# AM438x_EPOS_EVM_PMconnect.net
KiCad netlist of a schematic drawn in Altium Designer
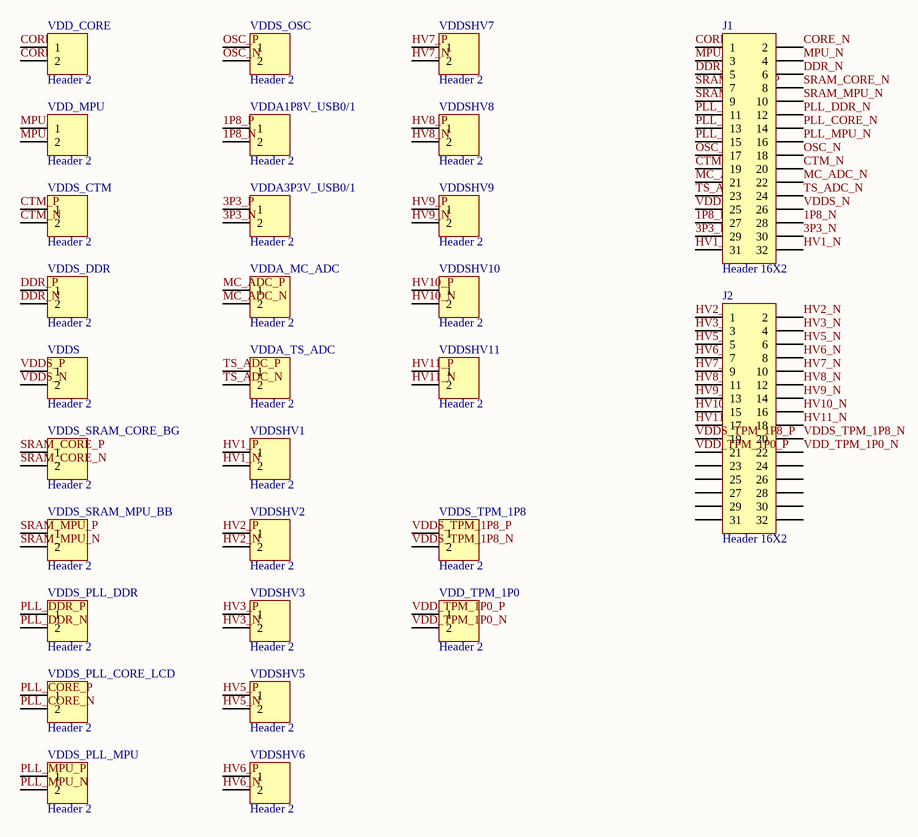
[diagram p0: AM438x_EPOS_EVM_PMconnect.SchDoc]

(export (version "E")
  (design (tool "Eeschema 10.0.6"))
  (components
    (comp (ref "J1")
      (value "Header 16X2")
      (footprint "HDR2X16")
      (description "Header, 16-Pin, Dual row")
      (fields (field (name "PUBLISHER") "Altium Limited"))
      (libsource (lib "Miscellaneous Connectors") (part "Header 16X2"))
    )
    (comp (ref "J2")
      (value "Header 16X2")
      (footprint "HDR2X16")
      (description "Header, 16-Pin, Dual row")
      (fields (field (name "PUBLISHER") "Altium Limited"))
      (libsource (lib "Miscellaneous Connectors") (part "Header 16X2"))
    )
    (comp (ref "VDDA1P8V_USB0/1")
      (value "Header 2")
      (footprint "HDR1X2")
      (description "Header, 2-Pin")
      (fields (field (name "PUBLISHER") "Altium Limited"))
      (libsource (lib "Miscellaneous Connectors") (part "Header 2"))
    )
    (comp (ref "VDDA3P3V_USB0/1")
      (value "Header 2")
      (footprint "HDR1X2")
      (description "Header, 2-Pin")
      (fields (field (name "PUBLISHER") "Altium Limited"))
      (libsource (lib "Miscellaneous Connectors") (part "Header 2"))
    )
    (comp (ref "VDDA_MC_ADC")
      (value "Header 2")
      (footprint "HDR1X2")
      (description "Header, 2-Pin")
      (fields (field (name "PUBLISHER") "Altium Limited"))
      (libsource (lib "Miscellaneous Connectors") (part "Header 2"))
    )
    (comp (ref "VDDA_TS_ADC")
      (value "Header 2")
      (footprint "HDR1X2")
      (description "Header, 2-Pin")
      (fields (field (name "PUBLISHER") "Altium Limited"))
      (libsource (lib "Miscellaneous Connectors") (part "Header 2"))
    )
    (comp (ref "VDDS")
      (value "Header 2")
      (footprint "HDR1X2")
      (description "Header, 2-Pin")
      (fields (field (name "PUBLISHER") "Altium Limited"))
      (libsource (lib "Miscellaneous Connectors") (part "Header 2"))
    )
    (comp (ref "VDDSHV1")
      (value "Header 2")
      (footprint "HDR1X2")
      (description "Header, 2-Pin")
      (fields (field (name "PUBLISHER") "Altium Limited"))
      (libsource (lib "Miscellaneous Connectors") (part "Header 2"))
    )
    (comp (ref "VDDSHV2")
      (value "Header 2")
      (footprint "HDR1X2")
      (description "Header, 2-Pin")
      (fields (field (name "PUBLISHER") "Altium Limited"))
      (libsource (lib "Miscellaneous Connectors") (part "Header 2"))
    )
    (comp (ref "VDDSHV3")
      (value "Header 2")
      (footprint "HDR1X2")
      (description "Header, 2-Pin")
      (fields (field (name "PUBLISHER") "Altium Limited"))
      (libsource (lib "Miscellaneous Connectors") (part "Header 2"))
    )
    (comp (ref "VDDSHV5")
      (value "Header 2")
      (footprint "HDR1X2")
      (description "Header, 2-Pin")
      (fields (field (name "PUBLISHER") "Altium Limited"))
      (libsource (lib "Miscellaneous Connectors") (part "Header 2"))
    )
    (comp (ref "VDDSHV6")
      (value "Header 2")
      (footprint "HDR1X2")
      (description "Header, 2-Pin")
      (fields (field (name "PUBLISHER") "Altium Limited"))
      (libsource (lib "Miscellaneous Connectors") (part "Header 2"))
    )
    (comp (ref "VDDSHV7")
      (value "Header 2")
      (footprint "HDR1X2")
      (description "Header, 2-Pin")
      (fields (field (name "PUBLISHER") "Altium Limited"))
      (libsource (lib "Miscellaneous Connectors") (part "Header 2"))
    )
    (comp (ref "VDDSHV8")
      (value "Header 2")
      (footprint "HDR1X2")
      (description "Header, 2-Pin")
      (fields (field (name "PUBLISHER") "Altium Limited"))
      (libsource (lib "Miscellaneous Connectors") (part "Header 2"))
    )
    (comp (ref "VDDSHV9")
      (value "Header 2")
      (footprint "HDR1X2")
      (description "Header, 2-Pin")
      (fields (field (name "PUBLISHER") "Altium Limited"))
      (libsource (lib "Miscellaneous Connectors") (part "Header 2"))
    )
    (comp (ref "VDDSHV10")
      (value "Header 2")
      (footprint "HDR1X2")
      (description "Header, 2-Pin")
      (fields (field (name "PUBLISHER") "Altium Limited"))
      (libsource (lib "Miscellaneous Connectors") (part "Header 2"))
    )
    (comp (ref "VDDSHV11")
      (value "Header 2")
      (footprint "HDR1X2")
      (description "Header, 2-Pin")
      (fields (field (name "PUBLISHER") "Altium Limited"))
      (libsource (lib "Miscellaneous Connectors") (part "Header 2"))
    )
    (comp (ref "VDDS_CTM")
      (value "Header 2")
      (footprint "HDR1X2")
      (description "Header, 2-Pin")
      (fields (field (name "PUBLISHER") "Altium Limited"))
      (libsource (lib "Miscellaneous Connectors") (part "Header 2"))
    )
    (comp (ref "VDDS_DDR")
      (value "Header 2")
      (footprint "HDR1X2")
      (description "Header, 2-Pin")
      (fields (field (name "PUBLISHER") "Altium Limited"))
      (libsource (lib "Miscellaneous Connectors") (part "Header 2"))
    )
    (comp (ref "VDDS_OSC")
      (value "Header 2")
      (footprint "HDR1X2")
      (description "Header, 2-Pin")
      (fields (field (name "PUBLISHER") "Altium Limited"))
      (libsource (lib "Miscellaneous Connectors") (part "Header 2"))
    )
    (comp (ref "VDDS_PLL_CORE_LCD")
      (value "Header 2")
      (footprint "HDR1X2")
      (description "Header, 2-Pin")
      (fields (field (name "PUBLISHER") "Altium Limited"))
      (libsource (lib "Miscellaneous Connectors") (part "Header 2"))
    )
    (comp (ref "VDDS_PLL_DDR")
      (value "Header 2")
      (footprint "HDR1X2")
      (description "Header, 2-Pin")
      (fields (field (name "PUBLISHER") "Altium Limited"))
      (libsource (lib "Miscellaneous Connectors") (part "Header 2"))
    )
    (comp (ref "VDDS_PLL_MPU")
      (value "Header 2")
      (footprint "HDR1X2")
      (description "Header, 2-Pin")
      (fields (field (name "PUBLISHER") "Altium Limited"))
      (libsource (lib "Miscellaneous Connectors") (part "Header 2"))
    )
    (comp (ref "VDDS_SRAM_CORE_BG")
      (value "Header 2")
      (footprint "HDR1X2")
      (description "Header, 2-Pin")
      (fields (field (name "PUBLISHER") "Altium Limited"))
      (libsource (lib "Miscellaneous Connectors") (part "Header 2"))
    )
    (comp (ref "VDDS_SRAM_MPU_BB")
      (value "Header 2")
      (footprint "HDR1X2")
      (description "Header, 2-Pin")
      (fields (field (name "PUBLISHER") "Altium Limited"))
      (libsource (lib "Miscellaneous Connectors") (part "Header 2"))
    )
    (comp (ref "VDDS_TPM_1P8")
      (value "Header 2")
      (footprint "HDR1X2")
      (description "Header, 2-Pin")
      (fields (field (name "PUBLISHER") "Altium Limited"))
      (libsource (lib "Miscellaneous Connectors") (part "Header 2"))
    )
    (comp (ref "VDD_CORE")
      (value "Header 2")
      (footprint "HDR1X2")
      (description "Header, 2-Pin")
      (fields (field (name "PUBLISHER") "Altium Limited"))
      (libsource (lib "Miscellaneous Connectors") (part "Header 2"))
    )
    (comp (ref "VDD_MPU")
      (value "Header 2")
      (footprint "HDR1X2")
      (description "Header, 2-Pin")
      (fields (field (name "PUBLISHER") "Altium Limited"))
      (libsource (lib "Miscellaneous Connectors") (part "Header 2"))
    )
    (comp (ref "VDD_TPM_1P0")
      (value "Header 2")
      (footprint "HDR1X2")
      (description "Header, 2-Pin")
      (fields (field (name "PUBLISHER") "Altium Limited"))
      (libsource (lib "Miscellaneous Connectors") (part "Header 2"))
    )
  )
  (nets
    (net (code "1") (name "/1P8_N") (class "Default")
      (node (ref "J1") (pin "28") (pinfunction "28_28") (pintype "passive"))
      (node (ref "VDDA1P8V_USB0/1") (pin "2") (pinfunction "2_2") (pintype "passive"))
    )
    (net (code "2") (name "/1P8_P") (class "Default")
      (node (ref "J1") (pin "27") (pinfunction "27_27") (pintype "passive"))
      (node (ref "VDDA1P8V_USB0/1") (pin "1") (pinfunction "1_1") (pintype "passive"))
    )
    (net (code "3") (name "/3P3_N") (class "Default")
      (node (ref "J1") (pin "30") (pinfunction "30_30") (pintype "passive"))
      (node (ref "VDDA3P3V_USB0/1") (pin "2") (pinfunction "2_2") (pintype "passive"))
    )
    (net (code "4") (name "/3P3_P") (class "Default")
      (node (ref "J1") (pin "29") (pinfunction "29_29") (pintype "passive"))
      (node (ref "VDDA3P3V_USB0/1") (pin "1") (pinfunction "1_1") (pintype "passive"))
    )
    (net (code "5") (name "/CORE_N") (class "Default")
      (node (ref "J1") (pin "2") (pinfunction "2_2") (pintype "passive"))
      (node (ref "VDD_CORE") (pin "2") (pinfunction "2_2") (pintype "passive"))
    )
    (net (code "6") (name "/CORE_P") (class "Default")
      (node (ref "J1") (pin "1") (pinfunction "1_1") (pintype "passive"))
      (node (ref "VDD_CORE") (pin "1") (pinfunction "1_1") (pintype "passive"))
    )
    (net (code "7") (name "/CTM_N") (class "Default")
      (node (ref "J1") (pin "20") (pinfunction "20_20") (pintype "passive"))
      (node (ref "VDDS_CTM") (pin "2") (pinfunction "2_2") (pintype "passive"))
    )
    (net (code "8") (name "/CTM_P") (class "Default")
      (node (ref "J1") (pin "19") (pinfunction "19_19") (pintype "passive"))
      (node (ref "VDDS_CTM") (pin "1") (pinfunction "1_1") (pintype "passive"))
    )
    (net (code "9") (name "/DDR_N") (class "Default")
      (node (ref "J1") (pin "6") (pinfunction "6_6") (pintype "passive"))
      (node (ref "VDDS_DDR") (pin "2") (pinfunction "2_2") (pintype "passive"))
    )
    (net (code "10") (name "/DDR_P") (class "Default")
      (node (ref "J1") (pin "5") (pinfunction "5_5") (pintype "passive"))
      (node (ref "VDDS_DDR") (pin "1") (pinfunction "1_1") (pintype "passive"))
    )
    (net (code "11") (name "/HV1_N") (class "Default")
      (node (ref "J1") (pin "32") (pinfunction "32_32") (pintype "passive"))
      (node (ref "VDDSHV1") (pin "2") (pinfunction "2_2") (pintype "passive"))
    )
    (net (code "12") (name "/HV1_P") (class "Default")
      (node (ref "J1") (pin "31") (pinfunction "31_31") (pintype "passive"))
      (node (ref "VDDSHV1") (pin "1") (pinfunction "1_1") (pintype "passive"))
    )
    (net (code "13") (name "/HV2_N") (class "Default")
      (node (ref "J2") (pin "2") (pinfunction "2_2") (pintype "passive"))
      (node (ref "VDDSHV2") (pin "2") (pinfunction "2_2") (pintype "passive"))
    )
    (net (code "14") (name "/HV2_P") (class "Default")
      (node (ref "J2") (pin "1") (pinfunction "1_1") (pintype "passive"))
      (node (ref "VDDSHV2") (pin "1") (pinfunction "1_1") (pintype "passive"))
    )
    (net (code "15") (name "/HV3_N") (class "Default")
      (node (ref "J2") (pin "4") (pinfunction "4_4") (pintype "passive"))
      (node (ref "VDDSHV3") (pin "2") (pinfunction "2_2") (pintype "passive"))
    )
    (net (code "16") (name "/HV3_P") (class "Default")
      (node (ref "J2") (pin "3") (pinfunction "3_3") (pintype "passive"))
      (node (ref "VDDSHV3") (pin "1") (pinfunction "1_1") (pintype "passive"))
    )
    (net (code "17") (name "/HV5_N") (class "Default")
      (node (ref "J2") (pin "6") (pinfunction "6_6") (pintype "passive"))
      (node (ref "VDDSHV5") (pin "2") (pinfunction "2_2") (pintype "passive"))
    )
    (net (code "18") (name "/HV5_P") (class "Default")
      (node (ref "J2") (pin "5") (pinfunction "5_5") (pintype "passive"))
      (node (ref "VDDSHV5") (pin "1") (pinfunction "1_1") (pintype "passive"))
    )
    (net (code "19") (name "/HV6_N") (class "Default")
      (node (ref "J2") (pin "8") (pinfunction "8_8") (pintype "passive"))
      (node (ref "VDDSHV6") (pin "2") (pinfunction "2_2") (pintype "passive"))
    )
    (net (code "20") (name "/HV6_P") (class "Default")
      (node (ref "J2") (pin "7") (pinfunction "7_7") (pintype "passive"))
      (node (ref "VDDSHV6") (pin "1") (pinfunction "1_1") (pintype "passive"))
    )
    (net (code "21") (name "/HV7_N") (class "Default")
      (node (ref "J2") (pin "10") (pinfunction "10_10") (pintype "passive"))
      (node (ref "VDDSHV7") (pin "2") (pinfunction "2_2") (pintype "passive"))
    )
    (net (code "22") (name "/HV7_P") (class "Default")
      (node (ref "J2") (pin "9") (pinfunction "9_9") (pintype "passive"))
      (node (ref "VDDSHV7") (pin "1") (pinfunction "1_1") (pintype "passive"))
    )
    (net (code "23") (name "/HV8_N") (class "Default")
      (node (ref "J2") (pin "12") (pinfunction "12_12") (pintype "passive"))
      (node (ref "VDDSHV8") (pin "2") (pinfunction "2_2") (pintype "passive"))
    )
    (net (code "24") (name "/HV8_P") (class "Default")
      (node (ref "J2") (pin "11") (pinfunction "11_11") (pintype "passive"))
      (node (ref "VDDSHV8") (pin "1") (pinfunction "1_1") (pintype "passive"))
    )
    (net (code "25") (name "/HV9_N") (class "Default")
      (node (ref "J2") (pin "14") (pinfunction "14_14") (pintype "passive"))
      (node (ref "VDDSHV9") (pin "2") (pinfunction "2_2") (pintype "passive"))
    )
    (net (code "26") (name "/HV9_P") (class "Default")
      (node (ref "J2") (pin "13") (pinfunction "13_13") (pintype "passive"))
      (node (ref "VDDSHV9") (pin "1") (pinfunction "1_1") (pintype "passive"))
    )
    (net (code "27") (name "/HV10_N") (class "Default")
      (node (ref "J2") (pin "16") (pinfunction "16_16") (pintype "passive"))
      (node (ref "VDDSHV10") (pin "2") (pinfunction "2_2") (pintype "passive"))
    )
    (net (code "28") (name "/HV10_P") (class "Default")
      (node (ref "J2") (pin "15") (pinfunction "15_15") (pintype "passive"))
      (node (ref "VDDSHV10") (pin "1") (pinfunction "1_1") (pintype "passive"))
    )
    (net (code "29") (name "/HV11_N") (class "Default")
      (node (ref "J2") (pin "18") (pinfunction "18_18") (pintype "passive"))
      (node (ref "VDDSHV11") (pin "2") (pinfunction "2_2") (pintype "passive"))
    )
    (net (code "30") (name "/HV11_P") (class "Default")
      (node (ref "J2") (pin "17") (pinfunction "17_17") (pintype "passive"))
      (node (ref "VDDSHV11") (pin "1") (pinfunction "1_1") (pintype "passive"))
    )
    (net (code "31") (name "/MC_ADC_N") (class "Default")
      (node (ref "J1") (pin "22") (pinfunction "22_22") (pintype "passive"))
      (node (ref "VDDA_MC_ADC") (pin "2") (pinfunction "2_2") (pintype "passive"))
    )
    (net (code "32") (name "/MC_ADC_P") (class "Default")
      (node (ref "J1") (pin "21") (pinfunction "21_21") (pintype "passive"))
      (node (ref "VDDA_MC_ADC") (pin "1") (pinfunction "1_1") (pintype "passive"))
    )
    (net (code "33") (name "/MPU_N") (class "Default")
      (node (ref "J1") (pin "4") (pinfunction "4_4") (pintype "passive"))
      (node (ref "VDD_MPU") (pin "2") (pinfunction "2_2") (pintype "passive"))
    )
    (net (code "34") (name "/MPU_P") (class "Default")
      (node (ref "J1") (pin "3") (pinfunction "3_3") (pintype "passive"))
      (node (ref "VDD_MPU") (pin "1") (pinfunction "1_1") (pintype "passive"))
    )
    (net (code "35") (name "/OSC_N") (class "Default")
      (node (ref "J1") (pin "18") (pinfunction "18_18") (pintype "passive"))
      (node (ref "VDDS_OSC") (pin "2") (pinfunction "2_2") (pintype "passive"))
    )
    (net (code "36") (name "/OSC_P") (class "Default")
      (node (ref "J1") (pin "17") (pinfunction "17_17") (pintype "passive"))
      (node (ref "VDDS_OSC") (pin "1") (pinfunction "1_1") (pintype "passive"))
    )
    (net (code "37") (name "/PLL_CORE_N") (class "Default")
      (node (ref "J1") (pin "14") (pinfunction "14_14") (pintype "passive"))
      (node (ref "VDDS_PLL_CORE_LCD") (pin "2") (pinfunction "2_2") (pintype "passive"))
    )
    (net (code "38") (name "/PLL_CORE_P") (class "Default")
      (node (ref "J1") (pin "13") (pinfunction "13_13") (pintype "passive"))
      (node (ref "VDDS_PLL_CORE_LCD") (pin "1") (pinfunction "1_1") (pintype "passive"))
    )
    (net (code "39") (name "/PLL_DDR_N") (class "Default")
      (node (ref "J1") (pin "12") (pinfunction "12_12") (pintype "passive"))
      (node (ref "VDDS_PLL_DDR") (pin "2") (pinfunction "2_2") (pintype "passive"))
    )
    (net (code "40") (name "/PLL_DDR_P") (class "Default")
      (node (ref "J1") (pin "11") (pinfunction "11_11") (pintype "passive"))
      (node (ref "VDDS_PLL_DDR") (pin "1") (pinfunction "1_1") (pintype "passive"))
    )
    (net (code "41") (name "/PLL_MPU_N") (class "Default")
      (node (ref "J1") (pin "16") (pinfunction "16_16") (pintype "passive"))
      (node (ref "VDDS_PLL_MPU") (pin "2") (pinfunction "2_2") (pintype "passive"))
    )
    (net (code "42") (name "/PLL_MPU_P") (class "Default")
      (node (ref "J1") (pin "15") (pinfunction "15_15") (pintype "passive"))
      (node (ref "VDDS_PLL_MPU") (pin "1") (pinfunction "1_1") (pintype "passive"))
    )
    (net (code "43") (name "/SRAM_CORE_N") (class "Default")
      (node (ref "J1") (pin "8") (pinfunction "8_8") (pintype "passive"))
      (node (ref "VDDS_SRAM_CORE_BG") (pin "2") (pinfunction "2_2") (pintype "passive"))
    )
    (net (code "44") (name "/SRAM_CORE_P") (class "Default")
      (node (ref "J1") (pin "7") (pinfunction "7_7") (pintype "passive"))
      (node (ref "VDDS_SRAM_CORE_BG") (pin "1") (pinfunction "1_1") (pintype "passive"))
    )
    (net (code "45") (name "/SRAM_MPU_N") (class "Default")
      (node (ref "J1") (pin "10") (pinfunction "10_10") (pintype "passive"))
      (node (ref "VDDS_SRAM_MPU_BB") (pin "2") (pinfunction "2_2") (pintype "passive"))
    )
    (net (code "46") (name "/SRAM_MPU_P") (class "Default")
      (node (ref "J1") (pin "9") (pinfunction "9_9") (pintype "passive"))
      (node (ref "VDDS_SRAM_MPU_BB") (pin "1") (pinfunction "1_1") (pintype "passive"))
    )
    (net (code "47") (name "/TS_ADC_N") (class "Default")
      (node (ref "J1") (pin "24") (pinfunction "24_24") (pintype "passive"))
      (node (ref "VDDA_TS_ADC") (pin "2") (pinfunction "2_2") (pintype "passive"))
    )
    (net (code "48") (name "/TS_ADC_P") (class "Default")
      (node (ref "J1") (pin "23") (pinfunction "23_23") (pintype "passive"))
      (node (ref "VDDA_TS_ADC") (pin "1") (pinfunction "1_1") (pintype "passive"))
    )
    (net (code "49") (name "/VDDS_N") (class "Default")
      (node (ref "J1") (pin "26") (pinfunction "26_26") (pintype "passive"))
      (node (ref "VDDS") (pin "2") (pinfunction "2_2") (pintype "passive"))
    )
    (net (code "50") (name "/VDDS_P") (class "Default")
      (node (ref "J1") (pin "25") (pinfunction "25_25") (pintype "passive"))
      (node (ref "VDDS") (pin "1") (pinfunction "1_1") (pintype "passive"))
    )
    (net (code "51") (name "/VDDS_TPM_1P8_N") (class "Default")
      (node (ref "J2") (pin "20") (pinfunction "20_20") (pintype "passive"))
      (node (ref "VDDS_TPM_1P8") (pin "2") (pinfunction "2_2") (pintype "passive"))
    )
    (net (code "52") (name "/VDDS_TPM_1P8_P") (class "Default")
      (node (ref "J2") (pin "19") (pinfunction "19_19") (pintype "passive"))
      (node (ref "VDDS_TPM_1P8") (pin "1") (pinfunction "1_1") (pintype "passive"))
    )
    (net (code "53") (name "/VDD_TPM_1P0_N") (class "Default")
      (node (ref "J2") (pin "22") (pinfunction "22_22") (pintype "passive"))
      (node (ref "VDD_TPM_1P0") (pin "2") (pinfunction "2_2") (pintype "passive"))
    )
    (net (code "54") (name "/VDD_TPM_1P0_P") (class "Default")
      (node (ref "J2") (pin "21") (pinfunction "21_21") (pintype "passive"))
      (node (ref "VDD_TPM_1P0") (pin "1") (pinfunction "1_1") (pintype "passive"))
    )
    (net (code "55") (name "unconnected-(J2-Pad23)") (class "Default")
      (node (ref "J2") (pin "23") (pinfunction "23_23") (pintype "passive"))
    )
    (net (code "56") (name "unconnected-(J2-Pad24)") (class "Default")
      (node (ref "J2") (pin "24") (pinfunction "24_24") (pintype "passive"))
    )
    (net (code "57") (name "unconnected-(J2-Pad25)") (class "Default")
      (node (ref "J2") (pin "25") (pinfunction "25_25") (pintype "passive"))
    )
    (net (code "58") (name "unconnected-(J2-Pad26)") (class "Default")
      (node (ref "J2") (pin "26") (pinfunction "26_26") (pintype "passive"))
    )
    (net (code "59") (name "unconnected-(J2-Pad27)") (class "Default")
      (node (ref "J2") (pin "27") (pinfunction "27_27") (pintype "passive"))
    )
    (net (code "60") (name "unconnected-(J2-Pad28)") (class "Default")
      (node (ref "J2") (pin "28") (pinfunction "28_28") (pintype "passive"))
    )
    (net (code "61") (name "unconnected-(J2-Pad29)") (class "Default")
      (node (ref "J2") (pin "29") (pinfunction "29_29") (pintype "passive"))
    )
    (net (code "62") (name "unconnected-(J2-Pad30)") (class "Default")
      (node (ref "J2") (pin "30") (pinfunction "30_30") (pintype "passive"))
    )
    (net (code "63") (name "unconnected-(J2-Pad31)") (class "Default")
      (node (ref "J2") (pin "31") (pinfunction "31_31") (pintype "passive"))
    )
    (net (code "64") (name "unconnected-(J2-Pad32)") (class "Default")
      (node (ref "J2") (pin "32") (pinfunction "32_32") (pintype "passive"))
    )
  )
)
